# IR.net
KiCad netlist of a schematic drawn in Altium Designer
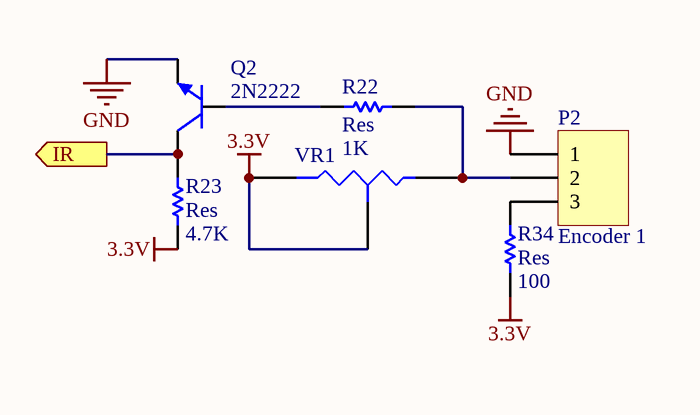
[diagram p0: IR.SchDoc]

(export (version "E")
  (design (tool "Eeschema 10.0.6"))
  (components
    (comp (ref "P2")
      (value "Encoder 1")
      (footprint "HDR1X3")
      (description "Header, 3-Pin")
      (fields (field (name "PUBLISHER") "Altium Limited"))
      (libsource (lib "KN2CLib") (part "Header 3"))
    )
    (comp (ref "Q2")
      (value "2N2222")
      (footprint "SOT-23")
      (description "NPN Bipolar Transistor")
      (fields (field (name "PUBLISHER") "Altium Limited"))
      (libsource (lib "KN2CLib") (part "2N2222"))
    )
    (comp (ref "R22")
      (value "Res")
      (footprint "2012[0805]")
      (description "Semiconductor Resistor")
      (fields (field (name "ALTIUM_VALUE") "1K") (field (name "PUBLISHER") "Altium Limited"))
      (libsource (lib "KN2CLib") (part "Res"))
    )
    (comp (ref "R23")
      (value "Res")
      (footprint "2012[0805]")
      (description "Semiconductor Resistor")
      (fields (field (name "ALTIUM_VALUE") "4.7K") (field (name "PUBLISHER") "Altium Limited"))
      (libsource (lib "KN2CLib") (part "Res"))
    )
    (comp (ref "R34")
      (value "Res")
      (footprint "2012[0805]")
      (description "Semiconductor Resistor")
      (fields (field (name "ALTIUM_VALUE") "100") (field (name "PUBLISHER") "Altium Limited"))
      (libsource (lib "KN2CLib") (part "Res"))
    )
    (comp (ref "VR1")
      (value "Res Tap")
      (footprint "MULTITURN")
      (description "Tapped Resistor")
      (fields (field (name "PUBLISHER") "Altium Limited"))
      (libsource (lib "KN2CLib") (part "Res Tap"))
    )
  )
  (nets
    (net (code "1") (name "/IR") (class "Default")
      (node (ref "Q2") (pin "1") (pinfunction "C_1") (pintype "passive"))
      (node (ref "R23") (pin "2") (pinfunction "2_2") (pintype "passive"))
    )
    (net (code "2") (name "3.3V") (class "Default")
      (node (ref "R23") (pin "1") (pinfunction "1_1") (pintype "passive"))
      (node (ref "R34") (pin "1") (pinfunction "1_1") (pintype "passive"))
      (node (ref "VR1") (pin "2") (pinfunction "B_2") (pintype "passive"))
      (node (ref "VR1") (pin "3") (pinfunction "TAP_3") (pintype "passive"))
    )
    (net (code "3") (name "GND") (class "Default")
      (node (ref "P2") (pin "1") (pinfunction "1_1") (pintype "passive"))
      (node (ref "Q2") (pin "3") (pinfunction "E_3") (pintype "passive"))
    )
    (net (code "4") (name "Net-(P2-Pad3)") (class "Default")
      (node (ref "P2") (pin "3") (pinfunction "3_3") (pintype "passive"))
      (node (ref "R34") (pin "2") (pinfunction "2_2") (pintype "passive"))
    )
    (net (code "5") (name "Net-(Q2-B)") (class "Default")
      (node (ref "Q2") (pin "2") (pinfunction "B_2") (pintype "passive"))
      (node (ref "R22") (pin "1") (pinfunction "1_1") (pintype "passive"))
    )
    (net (code "6") (name "Net-(VR1-A)") (class "Default")
      (node (ref "P2") (pin "2") (pinfunction "2_2") (pintype "passive"))
      (node (ref "R22") (pin "2") (pinfunction "2_2") (pintype "passive"))
      (node (ref "VR1") (pin "1") (pinfunction "A_1") (pintype "passive"))
    )
  )
)
